# room_controller3.net
KiCad netlist of a schematic drawn in EAGLE
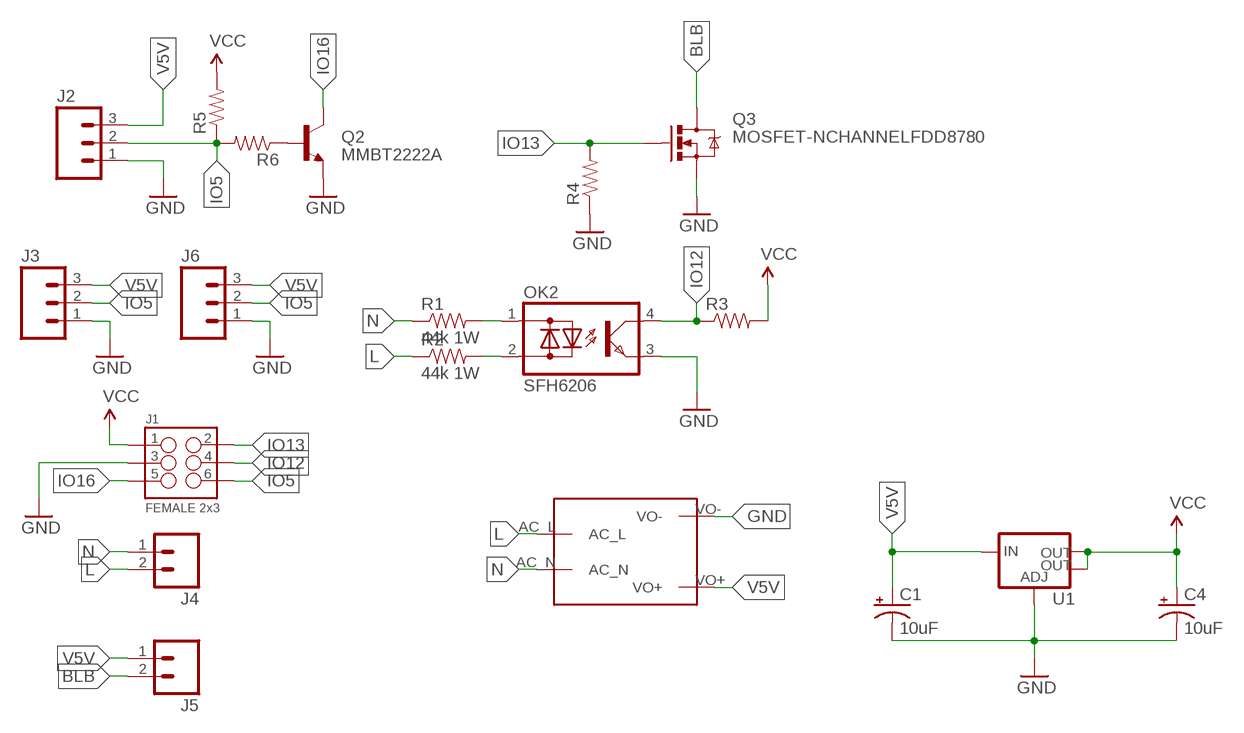
[diagram p0: schematic, sheet 1]

(export (version "E")
  (design (tool "Eeschema 10.0.6"))
  (components
    (comp (ref "C1")
      (value "10uF")
      (footprint "eagle-import:EIA3216-KIT")
      (libsource (lib "eagle-import") (part "CAP_POL1206-KIT"))
    )
    (comp (ref "C4")
      (value "10uF")
      (footprint "eagle-import:EIA3216-KIT")
      (libsource (lib "eagle-import") (part "CAP_POL1206-KIT"))
    )
    (comp (ref "J1")
      (value "FEMALE 2x3")
      (footprint "eagle-import:2X3-SHROUDED")
      (libsource (lib "eagle-import") (part "M03X2SHROUD"))
    )
    (comp (ref "J2")
      (value "M03PTH")
      (footprint "eagle-import:1X03")
      (libsource (lib "eagle-import") (part "M03PTH"))
    )
    (comp (ref "J3")
      (value "M03PTH")
      (footprint "eagle-import:1X03")
      (libsource (lib "eagle-import") (part "M03PTH"))
    )
    (comp (ref "J4")
      (value "M025MM")
      (footprint "eagle-import:SCREWTERMINAL-5MM-2")
      (libsource (lib "eagle-import") (part "M025MM"))
    )
    (comp (ref "J5")
      (value "M025MM")
      (footprint "eagle-import:SCREWTERMINAL-5MM-2")
      (libsource (lib "eagle-import") (part "M025MM"))
    )
    (comp (ref "J6")
      (value "M03PTH")
      (footprint "eagle-import:1X03")
      (libsource (lib "eagle-import") (part "M03PTH"))
    )
    (comp (ref "OK2")
      (value "SFH6206")
      (footprint "eagle-import:DIL4-SMD")
      (libsource (lib "eagle-import") (part "SFH6206"))
    )
    (comp (ref "Q2")
      (value "MMBT2222A")
      (footprint "eagle-import:SOT23-3")
      (libsource (lib "eagle-import") (part "TRANSISTOR_NPNMMBT2222A"))
    )
    (comp (ref "Q3")
      (value "MOSFET-NCHANNELFDD8780")
      (footprint "eagle-import:DPAK")
      (libsource (lib "eagle-import") (part "MOSFET-NCHANNELFDD8780"))
    )
    (comp (ref "R1")
      (value "44k 1W")
      (footprint "eagle-import:AXIAL-0.4")
      (libsource (lib "eagle-import") (part "SparkFun-Resistors_RESISTORPTH-1/4W"))
    )
    (comp (ref "R2")
      (value "44k 1W")
      (footprint "eagle-import:AXIAL-0.4")
      (libsource (lib "eagle-import") (part "SparkFun-Resistors_RESISTORPTH-1/4W"))
    )
    (comp (ref "R3")
      (value "RESISTOR0805-RES")
      (footprint "eagle-import:0805")
      (libsource (lib "eagle-import") (part "RESISTOR0805-RES"))
    )
    (comp (ref "R4")
      (value "RESISTOR0805-RES")
      (footprint "eagle-import:0805")
      (libsource (lib "eagle-import") (part "RESISTOR0805-RES"))
    )
    (comp (ref "R5")
      (value "RESISTOR0805-RES")
      (footprint "eagle-import:0805")
      (libsource (lib "eagle-import") (part "RESISTOR0805-RES"))
    )
    (comp (ref "R6")
      (value "RESISTOR0805-RES")
      (footprint "eagle-import:0805")
      (libsource (lib "eagle-import") (part "RESISTOR0805-RES"))
    )
    (comp (ref "U$1")
      (value "MAINS_CONVERTERS")
      (footprint "eagle-import:HLK-PM01")
      (libsource (lib "eagle-import") (part "MAINS_CONVERTERS"))
    )
    (comp (ref "U1")
      (value "V_REG_LM1117SOT223")
      (footprint "eagle-import:SOT223")
      (libsource (lib "eagle-import") (part "V_REG_LM1117SOT223"))
    )
  )
  (nets
    (net (code "1") (name "BLB") (class "Default")
      (node (ref "J5") (pin "2") (pinfunction "2_2") (pintype "passive"))
      (node (ref "Q3") (pin "4") (pinfunction "D_4") (pintype "passive"))
    )
    (net (code "2") (name "GND") (class "Default")
      (node (ref "C1") (pin "C") (pinfunction "-_C") (pintype "passive"))
      (node (ref "C4") (pin "C") (pinfunction "-_C") (pintype "passive"))
      (node (ref "J1") (pin "3") (pinfunction "3_3") (pintype "bidirectional"))
      (node (ref "J2") (pin "1") (pinfunction "1_1") (pintype "passive"))
      (node (ref "J3") (pin "1") (pinfunction "1_1") (pintype "passive"))
      (node (ref "J6") (pin "1") (pinfunction "1_1") (pintype "passive"))
      (node (ref "OK2") (pin "3") (pinfunction "E_3") (pintype "passive"))
      (node (ref "Q2") (pin "2") (pinfunction "E_2") (pintype "passive"))
      (node (ref "Q3") (pin "3") (pinfunction "S_3") (pintype "passive"))
      (node (ref "R4") (pin "1") (pinfunction "1_1") (pintype "passive"))
      (node (ref "U$1") (pin "VO-") (pinfunction "VO-_VO-") (pintype "output"))
      (node (ref "U1") (pin "1") (pinfunction "ADJ_1") (pintype "input"))
    )
    (net (code "3") (name "IO5") (class "Default")
      (node (ref "J1") (pin "6") (pinfunction "6_6") (pintype "bidirectional"))
      (node (ref "J2") (pin "2") (pinfunction "2_2") (pintype "passive"))
      (node (ref "J3") (pin "2") (pinfunction "2_2") (pintype "passive"))
      (node (ref "J6") (pin "2") (pinfunction "2_2") (pintype "passive"))
      (node (ref "R5") (pin "1") (pinfunction "1_1") (pintype "passive"))
      (node (ref "R6") (pin "2") (pinfunction "2_2") (pintype "passive"))
    )
    (net (code "4") (name "IO12") (class "Default")
      (node (ref "J1") (pin "4") (pinfunction "4_4") (pintype "bidirectional"))
      (node (ref "OK2") (pin "4") (pinfunction "C_4") (pintype "passive"))
      (node (ref "R3") (pin "1") (pinfunction "1_1") (pintype "passive"))
    )
    (net (code "5") (name "IO13") (class "Default")
      (node (ref "J1") (pin "2") (pinfunction "2_2") (pintype "bidirectional"))
      (node (ref "Q3") (pin "1") (pinfunction "G_1") (pintype "passive"))
      (node (ref "R4") (pin "2") (pinfunction "2_2") (pintype "passive"))
    )
    (net (code "6") (name "IO16") (class "Default")
      (node (ref "J1") (pin "5") (pinfunction "5_5") (pintype "bidirectional"))
      (node (ref "Q2") (pin "3") (pinfunction "C_3") (pintype "passive"))
    )
    (net (code "7") (name "L") (class "Default")
      (node (ref "J4") (pin "2") (pinfunction "2_2") (pintype "passive"))
      (node (ref "R2") (pin "P$1") (pinfunction "1_P$1") (pintype "passive"))
      (node (ref "U$1") (pin "AC_L") (pinfunction "AC_L_AC_L") (pintype "input"))
    )
    (net (code "8") (name "N") (class "Default")
      (node (ref "J4") (pin "1") (pinfunction "1_1") (pintype "passive"))
      (node (ref "R1") (pin "P$1") (pinfunction "1_P$1") (pintype "passive"))
      (node (ref "U$1") (pin "AC_N") (pinfunction "AC_N_AC_N") (pintype "input"))
    )
    (net (code "9") (name "Net-(OK2-AC1)") (class "Default")
      (node (ref "OK2") (pin "1") (pinfunction "AC1_1") (pintype "passive"))
      (node (ref "R1") (pin "P$2") (pinfunction "2_P$2") (pintype "passive"))
    )
    (net (code "10") (name "Net-(OK2-AC2)") (class "Default")
      (node (ref "OK2") (pin "2") (pinfunction "AC2_2") (pintype "passive"))
      (node (ref "R2") (pin "P$2") (pinfunction "2_P$2") (pintype "passive"))
    )
    (net (code "11") (name "Net-(Q2-B)") (class "Default")
      (node (ref "Q2") (pin "1") (pinfunction "B_1") (pintype "passive"))
      (node (ref "R6") (pin "1") (pinfunction "1_1") (pintype "passive"))
    )
    (net (code "12") (name "V5V") (class "Default")
      (node (ref "C1") (pin "A") (pinfunction "+_A") (pintype "passive"))
      (node (ref "J2") (pin "3") (pinfunction "3_3") (pintype "passive"))
      (node (ref "J3") (pin "3") (pinfunction "3_3") (pintype "passive"))
      (node (ref "J5") (pin "1") (pinfunction "1_1") (pintype "passive"))
      (node (ref "J6") (pin "3") (pinfunction "3_3") (pintype "passive"))
      (node (ref "U$1") (pin "VO+") (pinfunction "VO+_VO+") (pintype "output"))
      (node (ref "U1") (pin "3") (pinfunction "IN_3") (pintype "input"))
    )
    (net (code "13") (name "VCC") (class "Default")
      (node (ref "C4") (pin "A") (pinfunction "+_A") (pintype "passive"))
      (node (ref "J1") (pin "1") (pinfunction "1_1") (pintype "bidirectional"))
      (node (ref "R3") (pin "2") (pinfunction "2_2") (pintype "passive"))
      (node (ref "R5") (pin "2") (pinfunction "2_2") (pintype "passive"))
      (node (ref "U1") (pin "2") (pinfunction "OUT_2") (pintype "output"))
      (node (ref "U1") (pin "4") (pinfunction "OUT_4") (pintype "output"))
    )
  )
)
